# SOCDDR3Bank.net
KiCad netlist of a schematic drawn in Altium Designer
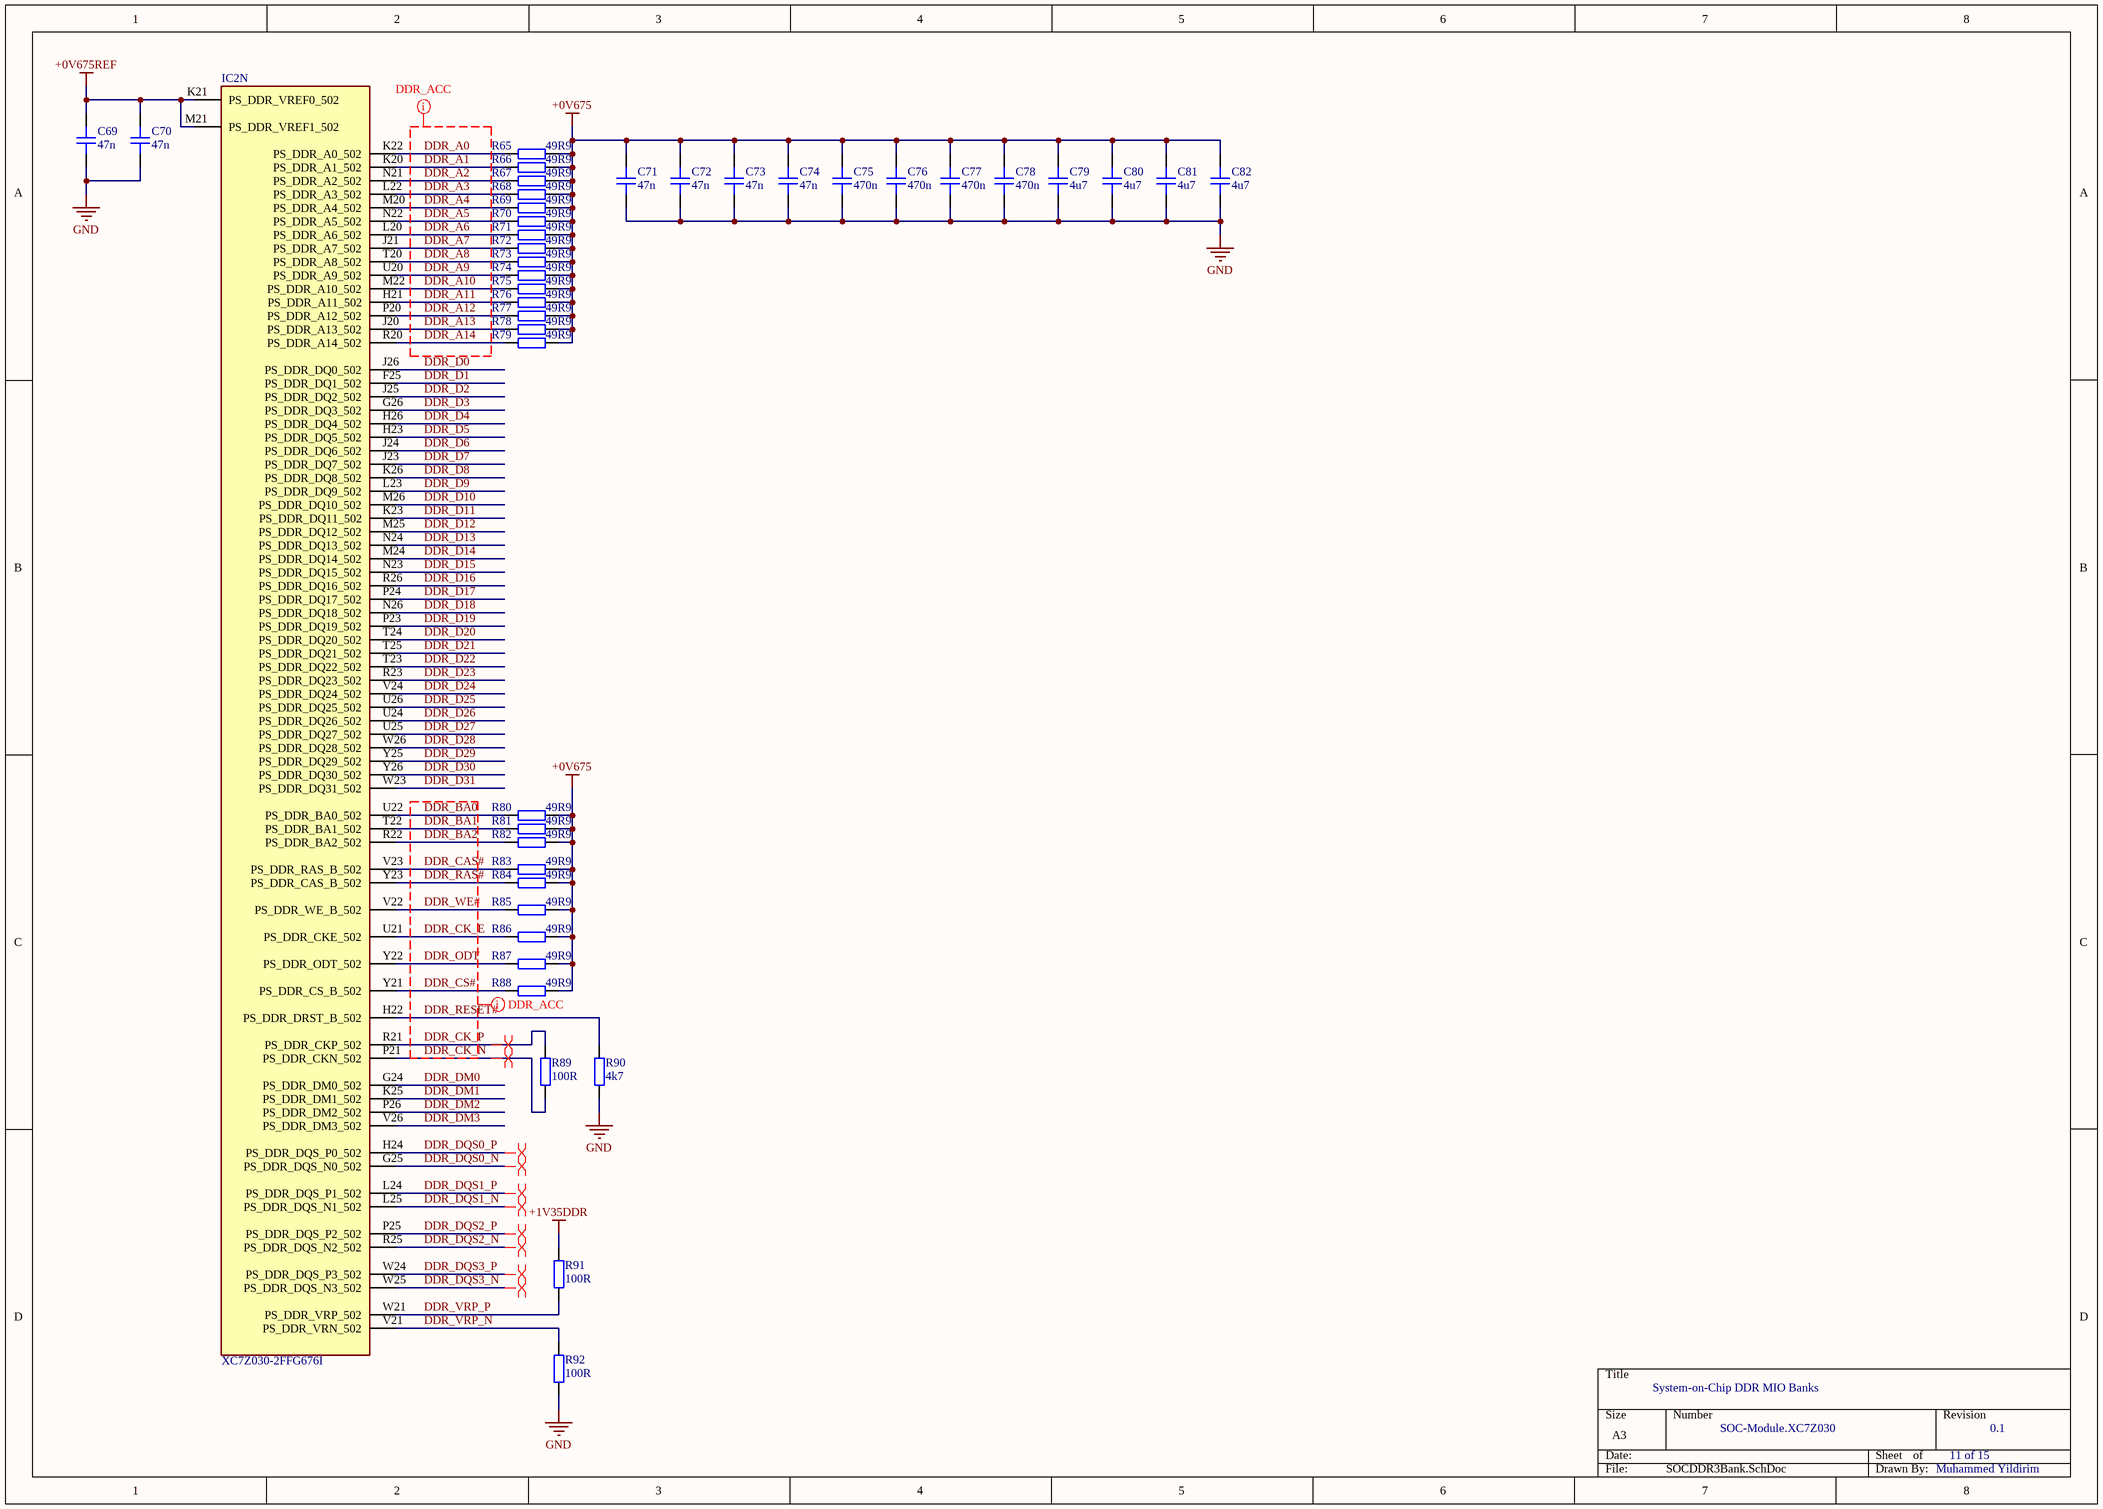
[diagram p0: SOCDDR3Bank.SchDoc]

(export (version "E")
  (design (tool "Eeschema 10.0.6"))
  (components
    (comp (ref "C69")
      (value "47n")
      (footprint "CAP_0201")
      (description "Capacitor SMD 0201")
      (libsource (lib "Schematic-Lib-PhilsLab") (part "CAP_0201"))
    )
    (comp (ref "C70")
      (value "47n")
      (footprint "CAP_0201")
      (description "Capacitor SMD 0201")
      (libsource (lib "Schematic-Lib-PhilsLab") (part "CAP_0201"))
    )
    (comp (ref "C71")
      (value "47n")
      (footprint "CAP_0201")
      (description "Capacitor SMD 0201")
      (libsource (lib "Schematic-Lib-PhilsLab") (part "CAP_0201"))
    )
    (comp (ref "C72")
      (value "47n")
      (footprint "CAP_0201")
      (description "Capacitor SMD 0201")
      (libsource (lib "Schematic-Lib-PhilsLab") (part "CAP_0201"))
    )
    (comp (ref "C73")
      (value "47n")
      (footprint "CAP_0201")
      (description "Capacitor SMD 0201")
      (libsource (lib "Schematic-Lib-PhilsLab") (part "CAP_0201"))
    )
    (comp (ref "C74")
      (value "47n")
      (footprint "CAP_0201")
      (description "Capacitor SMD 0201")
      (libsource (lib "Schematic-Lib-PhilsLab") (part "CAP_0201"))
    )
    (comp (ref "C75")
      (value "470n")
      (footprint "CAP_0201")
      (description "Capacitor SMD 0201")
      (libsource (lib "Schematic-Lib-PhilsLab") (part "CAP_0201"))
    )
    (comp (ref "C76")
      (value "470n")
      (footprint "CAP_0201")
      (description "Capacitor SMD 0201")
      (libsource (lib "Schematic-Lib-PhilsLab") (part "CAP_0201"))
    )
    (comp (ref "C77")
      (value "470n")
      (footprint "CAP_0201")
      (description "Capacitor SMD 0201")
      (libsource (lib "Schematic-Lib-PhilsLab") (part "CAP_0201"))
    )
    (comp (ref "C78")
      (value "470n")
      (footprint "CAP_0201")
      (description "Capacitor SMD 0201")
      (libsource (lib "Schematic-Lib-PhilsLab") (part "CAP_0201"))
    )
    (comp (ref "C79")
      (value "4u7")
      (footprint "CAP_0402")
      (description "Capacitor SMD 0402")
      (libsource (lib "Schematic-Lib-PhilsLab") (part "CAP_0402"))
    )
    (comp (ref "C80")
      (value "4u7")
      (footprint "CAP_0402")
      (description "Capacitor SMD 0402")
      (libsource (lib "Schematic-Lib-PhilsLab") (part "CAP_0402"))
    )
    (comp (ref "C81")
      (value "4u7")
      (footprint "CAP_0402")
      (description "Capacitor SMD 0402")
      (libsource (lib "Schematic-Lib-PhilsLab") (part "CAP_0402"))
    )
    (comp (ref "C82")
      (value "4u7")
      (footprint "CAP_0402")
      (description "Capacitor SMD 0402")
      (libsource (lib "Schematic-Lib-PhilsLab") (part "CAP_0402"))
    )
    (comp (ref "IC2")
      (value "XC7Z030-2FFG676I")
      (footprint "XC7Z030PCBLib:BGA676C100P26X26_2700X2700X324")
      (description "Integrated Circuit")
      (fields (field (name "MOUSER PART NUMBER") "217-XC7Z030-2FFG676I"))
      (libsource (lib "XC7Z030SCHLib") (part "XC7Z030-2FFG676I"))
    )
    (comp (ref "R65")
      (value "49R9")
      (footprint "RES_0201")
      (description "Resistor SMD 0201")
      (libsource (lib "Schematic-Lib-PhilsLab") (part "RES_0201"))
    )
    (comp (ref "R66")
      (value "49R9")
      (footprint "RES_0201")
      (description "Resistor SMD 0201")
      (libsource (lib "Schematic-Lib-PhilsLab") (part "RES_0201"))
    )
    (comp (ref "R67")
      (value "49R9")
      (footprint "RES_0201")
      (description "Resistor SMD 0201")
      (libsource (lib "Schematic-Lib-PhilsLab") (part "RES_0201"))
    )
    (comp (ref "R68")
      (value "49R9")
      (footprint "RES_0201")
      (description "Resistor SMD 0201")
      (libsource (lib "Schematic-Lib-PhilsLab") (part "RES_0201"))
    )
    (comp (ref "R69")
      (value "49R9")
      (footprint "RES_0201")
      (description "Resistor SMD 0201")
      (libsource (lib "Schematic-Lib-PhilsLab") (part "RES_0201"))
    )
    (comp (ref "R70")
      (value "49R9")
      (footprint "RES_0201")
      (description "Resistor SMD 0201")
      (libsource (lib "Schematic-Lib-PhilsLab") (part "RES_0201"))
    )
    (comp (ref "R71")
      (value "49R9")
      (footprint "RES_0201")
      (description "Resistor SMD 0201")
      (libsource (lib "Schematic-Lib-PhilsLab") (part "RES_0201"))
    )
    (comp (ref "R72")
      (value "49R9")
      (footprint "RES_0201")
      (description "Resistor SMD 0201")
      (libsource (lib "Schematic-Lib-PhilsLab") (part "RES_0201"))
    )
    (comp (ref "R73")
      (value "49R9")
      (footprint "RES_0201")
      (description "Resistor SMD 0201")
      (libsource (lib "Schematic-Lib-PhilsLab") (part "RES_0201"))
    )
    (comp (ref "R74")
      (value "49R9")
      (footprint "RES_0201")
      (description "Resistor SMD 0201")
      (libsource (lib "Schematic-Lib-PhilsLab") (part "RES_0201"))
    )
    (comp (ref "R75")
      (value "49R9")
      (footprint "RES_0201")
      (description "Resistor SMD 0201")
      (libsource (lib "Schematic-Lib-PhilsLab") (part "RES_0201"))
    )
    (comp (ref "R76")
      (value "49R9")
      (footprint "RES_0201")
      (description "Resistor SMD 0201")
      (libsource (lib "Schematic-Lib-PhilsLab") (part "RES_0201"))
    )
    (comp (ref "R77")
      (value "49R9")
      (footprint "RES_0201")
      (description "Resistor SMD 0201")
      (libsource (lib "Schematic-Lib-PhilsLab") (part "RES_0201"))
    )
    (comp (ref "R78")
      (value "49R9")
      (footprint "RES_0201")
      (description "Resistor SMD 0201")
      (libsource (lib "Schematic-Lib-PhilsLab") (part "RES_0201"))
    )
    (comp (ref "R79")
      (value "49R9")
      (footprint "RES_0201")
      (description "Resistor SMD 0201")
      (libsource (lib "Schematic-Lib-PhilsLab") (part "RES_0201"))
    )
    (comp (ref "R80")
      (value "49R9")
      (footprint "RES_0201")
      (description "Resistor SMD 0201")
      (libsource (lib "Schematic-Lib-PhilsLab") (part "RES_0201"))
    )
    (comp (ref "R81")
      (value "49R9")
      (footprint "RES_0201")
      (description "Resistor SMD 0201")
      (libsource (lib "Schematic-Lib-PhilsLab") (part "RES_0201"))
    )
    (comp (ref "R82")
      (value "49R9")
      (footprint "RES_0201")
      (description "Resistor SMD 0201")
      (libsource (lib "Schematic-Lib-PhilsLab") (part "RES_0201"))
    )
    (comp (ref "R83")
      (value "49R9")
      (footprint "RES_0201")
      (description "Resistor SMD 0201")
      (libsource (lib "Schematic-Lib-PhilsLab") (part "RES_0201"))
    )
    (comp (ref "R84")
      (value "49R9")
      (footprint "RES_0201")
      (description "Resistor SMD 0201")
      (libsource (lib "Schematic-Lib-PhilsLab") (part "RES_0201"))
    )
    (comp (ref "R85")
      (value "49R9")
      (footprint "RES_0201")
      (description "Resistor SMD 0201")
      (libsource (lib "Schematic-Lib-PhilsLab") (part "RES_0201"))
    )
    (comp (ref "R86")
      (value "49R9")
      (footprint "RES_0201")
      (description "Resistor SMD 0201")
      (libsource (lib "Schematic-Lib-PhilsLab") (part "RES_0201"))
    )
    (comp (ref "R87")
      (value "49R9")
      (footprint "RES_0201")
      (description "Resistor SMD 0201")
      (libsource (lib "Schematic-Lib-PhilsLab") (part "RES_0201"))
    )
    (comp (ref "R88")
      (value "49R9")
      (footprint "RES_0201")
      (description "Resistor SMD 0201")
      (libsource (lib "Schematic-Lib-PhilsLab") (part "RES_0201"))
    )
    (comp (ref "R89")
      (value "100R")
      (footprint "RES_0201")
      (description "Resistor SMD 0201")
      (libsource (lib "Schematic-Lib-PhilsLab") (part "RES_0201"))
    )
    (comp (ref "R90")
      (value "4k7")
      (footprint "RES_0201")
      (description "Resistor SMD 0201")
      (libsource (lib "Schematic-Lib-PhilsLab") (part "RES_0201"))
    )
    (comp (ref "R91")
      (value "100R")
      (footprint "RES_0201")
      (description "Resistor SMD 0201")
      (libsource (lib "Schematic-Lib-PhilsLab") (part "RES_0201"))
    )
    (comp (ref "R92")
      (value "100R")
      (footprint "RES_0201")
      (description "Resistor SMD 0201")
      (libsource (lib "Schematic-Lib-PhilsLab") (part "RES_0201"))
    )
  )
  (nets
    (net (code "1") (name "+0V675") (class "Default")
      (node (ref "C71") (pin "2") (pinfunction "2_2") (pintype "passive"))
      (node (ref "C72") (pin "2") (pinfunction "2_2") (pintype "passive"))
      (node (ref "C73") (pin "2") (pinfunction "2_2") (pintype "passive"))
      (node (ref "C74") (pin "2") (pinfunction "2_2") (pintype "passive"))
      (node (ref "C75") (pin "2") (pinfunction "2_2") (pintype "passive"))
      (node (ref "C76") (pin "2") (pinfunction "2_2") (pintype "passive"))
      (node (ref "C77") (pin "2") (pinfunction "2_2") (pintype "passive"))
      (node (ref "C78") (pin "2") (pinfunction "2_2") (pintype "passive"))
      (node (ref "C79") (pin "2") (pinfunction "2_2") (pintype "passive"))
      (node (ref "C80") (pin "2") (pinfunction "2_2") (pintype "passive"))
      (node (ref "C81") (pin "2") (pinfunction "2_2") (pintype "passive"))
      (node (ref "C82") (pin "2") (pinfunction "2_2") (pintype "passive"))
      (node (ref "R65") (pin "1") (pinfunction "1_1") (pintype "passive"))
      (node (ref "R66") (pin "1") (pinfunction "1_1") (pintype "passive"))
      (node (ref "R67") (pin "1") (pinfunction "1_1") (pintype "passive"))
      (node (ref "R68") (pin "1") (pinfunction "1_1") (pintype "passive"))
      (node (ref "R69") (pin "1") (pinfunction "1_1") (pintype "passive"))
      (node (ref "R70") (pin "1") (pinfunction "1_1") (pintype "passive"))
      (node (ref "R71") (pin "1") (pinfunction "1_1") (pintype "passive"))
      (node (ref "R72") (pin "1") (pinfunction "1_1") (pintype "passive"))
      (node (ref "R73") (pin "1") (pinfunction "1_1") (pintype "passive"))
      (node (ref "R74") (pin "1") (pinfunction "1_1") (pintype "passive"))
      (node (ref "R75") (pin "1") (pinfunction "1_1") (pintype "passive"))
      (node (ref "R76") (pin "1") (pinfunction "1_1") (pintype "passive"))
      (node (ref "R77") (pin "1") (pinfunction "1_1") (pintype "passive"))
      (node (ref "R78") (pin "1") (pinfunction "1_1") (pintype "passive"))
      (node (ref "R79") (pin "1") (pinfunction "1_1") (pintype "passive"))
      (node (ref "R80") (pin "1") (pinfunction "1_1") (pintype "passive"))
      (node (ref "R81") (pin "1") (pinfunction "1_1") (pintype "passive"))
      (node (ref "R82") (pin "1") (pinfunction "1_1") (pintype "passive"))
      (node (ref "R83") (pin "1") (pinfunction "1_1") (pintype "passive"))
      (node (ref "R84") (pin "1") (pinfunction "1_1") (pintype "passive"))
      (node (ref "R85") (pin "1") (pinfunction "1_1") (pintype "passive"))
      (node (ref "R86") (pin "1") (pinfunction "1_1") (pintype "passive"))
      (node (ref "R87") (pin "1") (pinfunction "1_1") (pintype "passive"))
      (node (ref "R88") (pin "1") (pinfunction "1_1") (pintype "passive"))
    )
    (net (code "2") (name "+0V675REF") (class "Default")
      (node (ref "C69") (pin "2") (pinfunction "2_2") (pintype "passive"))
      (node (ref "C70") (pin "2") (pinfunction "2_2") (pintype "passive"))
      (node (ref "IC2") (pin "K21") (pinfunction "PS_DDR_VREF0_502_K21") (pintype "passive"))
      (node (ref "IC2") (pin "M21") (pinfunction "PS_DDR_VREF1_502_M21") (pintype "passive"))
    )
    (net (code "3") (name "+1V35DDR") (class "Default")
      (node (ref "R91") (pin "2") (pinfunction "2_2") (pintype "passive"))
    )
    (net (code "4") (name "/DDR_A0") (class "Default")
      (node (ref "IC2") (pin "K22") (pinfunction "PS_DDR_A0_502_K22") (pintype "passive"))
      (node (ref "R65") (pin "2") (pinfunction "2_2") (pintype "passive"))
    )
    (net (code "5") (name "/DDR_A1") (class "Default")
      (node (ref "IC2") (pin "K20") (pinfunction "PS_DDR_A1_502_K20") (pintype "passive"))
      (node (ref "R66") (pin "2") (pinfunction "2_2") (pintype "passive"))
    )
    (net (code "6") (name "/DDR_A2") (class "Default")
      (node (ref "IC2") (pin "N21") (pinfunction "PS_DDR_A2_502_N21") (pintype "passive"))
      (node (ref "R67") (pin "2") (pinfunction "2_2") (pintype "passive"))
    )
    (net (code "7") (name "/DDR_A3") (class "Default")
      (node (ref "IC2") (pin "L22") (pinfunction "PS_DDR_A3_502_L22") (pintype "passive"))
      (node (ref "R68") (pin "2") (pinfunction "2_2") (pintype "passive"))
    )
    (net (code "8") (name "/DDR_A4") (class "Default")
      (node (ref "IC2") (pin "M20") (pinfunction "PS_DDR_A4_502_M20") (pintype "passive"))
      (node (ref "R69") (pin "2") (pinfunction "2_2") (pintype "passive"))
    )
    (net (code "9") (name "/DDR_A5") (class "Default")
      (node (ref "IC2") (pin "N22") (pinfunction "PS_DDR_A5_502_N22") (pintype "passive"))
      (node (ref "R70") (pin "2") (pinfunction "2_2") (pintype "passive"))
    )
    (net (code "10") (name "/DDR_A6") (class "Default")
      (node (ref "IC2") (pin "L20") (pinfunction "PS_DDR_A6_502_L20") (pintype "passive"))
      (node (ref "R71") (pin "2") (pinfunction "2_2") (pintype "passive"))
    )
    (net (code "11") (name "/DDR_A7") (class "Default")
      (node (ref "IC2") (pin "J21") (pinfunction "PS_DDR_A7_502_J21") (pintype "passive"))
      (node (ref "R72") (pin "2") (pinfunction "2_2") (pintype "passive"))
    )
    (net (code "12") (name "/DDR_A8") (class "Default")
      (node (ref "IC2") (pin "T20") (pinfunction "PS_DDR_A8_502_T20") (pintype "passive"))
      (node (ref "R73") (pin "2") (pinfunction "2_2") (pintype "passive"))
    )
    (net (code "13") (name "/DDR_A9") (class "Default")
      (node (ref "IC2") (pin "U20") (pinfunction "PS_DDR_A9_502_U20") (pintype "passive"))
      (node (ref "R74") (pin "2") (pinfunction "2_2") (pintype "passive"))
    )
    (net (code "14") (name "/DDR_A10") (class "Default")
      (node (ref "IC2") (pin "M22") (pinfunction "PS_DDR_A10_502_M22") (pintype "passive"))
      (node (ref "R75") (pin "2") (pinfunction "2_2") (pintype "passive"))
    )
    (net (code "15") (name "/DDR_A11") (class "Default")
      (node (ref "IC2") (pin "H21") (pinfunction "PS_DDR_A11_502_H21") (pintype "passive"))
      (node (ref "R76") (pin "2") (pinfunction "2_2") (pintype "passive"))
    )
    (net (code "16") (name "/DDR_A12") (class "Default")
      (node (ref "IC2") (pin "P20") (pinfunction "PS_DDR_A12_502_P20") (pintype "passive"))
      (node (ref "R77") (pin "2") (pinfunction "2_2") (pintype "passive"))
    )
    (net (code "17") (name "/DDR_A13") (class "Default")
      (node (ref "IC2") (pin "J20") (pinfunction "PS_DDR_A13_502_J20") (pintype "passive"))
      (node (ref "R78") (pin "2") (pinfunction "2_2") (pintype "passive"))
    )
    (net (code "18") (name "/DDR_A14") (class "Default")
      (node (ref "IC2") (pin "R20") (pinfunction "PS_DDR_A14_502_R20") (pintype "passive"))
      (node (ref "R79") (pin "2") (pinfunction "2_2") (pintype "passive"))
    )
    (net (code "19") (name "/DDR_BA0") (class "Default")
      (node (ref "IC2") (pin "U22") (pinfunction "PS_DDR_BA0_502_U22") (pintype "passive"))
      (node (ref "R80") (pin "2") (pinfunction "2_2") (pintype "passive"))
    )
    (net (code "20") (name "/DDR_BA1") (class "Default")
      (node (ref "IC2") (pin "T22") (pinfunction "PS_DDR_BA1_502_T22") (pintype "passive"))
      (node (ref "R81") (pin "2") (pinfunction "2_2") (pintype "passive"))
    )
    (net (code "21") (name "/DDR_BA2") (class "Default")
      (node (ref "IC2") (pin "R22") (pinfunction "PS_DDR_BA2_502_R22") (pintype "passive"))
      (node (ref "R82") (pin "2") (pinfunction "2_2") (pintype "passive"))
    )
    (net (code "22") (name "/DDR_CAS#") (class "Default")
      (node (ref "IC2") (pin "V23") (pinfunction "PS_DDR_RAS_B_502_V23") (pintype "passive"))
      (node (ref "R83") (pin "2") (pinfunction "2_2") (pintype "passive"))
    )
    (net (code "23") (name "/DDR_CK_E") (class "Default")
      (node (ref "IC2") (pin "U21") (pinfunction "PS_DDR_CKE_502_U21") (pintype "passive"))
      (node (ref "R86") (pin "2") (pinfunction "2_2") (pintype "passive"))
    )
    (net (code "24") (name "/DDR_CK_N") (class "Default")
      (node (ref "IC2") (pin "P21") (pinfunction "PS_DDR_CKN_502_P21") (pintype "passive"))
      (node (ref "R89") (pin "1") (pinfunction "1_1") (pintype "passive"))
    )
    (net (code "25") (name "/DDR_CK_P") (class "Default")
      (node (ref "IC2") (pin "R21") (pinfunction "PS_DDR_CKP_502_R21") (pintype "passive"))
      (node (ref "R89") (pin "2") (pinfunction "2_2") (pintype "passive"))
    )
    (net (code "26") (name "/DDR_CS#") (class "Default")
      (node (ref "IC2") (pin "Y21") (pinfunction "PS_DDR_CS_B_502_Y21") (pintype "passive"))
      (node (ref "R88") (pin "2") (pinfunction "2_2") (pintype "passive"))
    )
    (net (code "27") (name "/DDR_D0") (class "Default")
      (node (ref "IC2") (pin "J26") (pinfunction "PS_DDR_DQ0_502_J26") (pintype "passive"))
    )
    (net (code "28") (name "/DDR_D1") (class "Default")
      (node (ref "IC2") (pin "F25") (pinfunction "PS_DDR_DQ1_502_F25") (pintype "passive"))
    )
    (net (code "29") (name "/DDR_D2") (class "Default")
      (node (ref "IC2") (pin "J25") (pinfunction "PS_DDR_DQ2_502_J25") (pintype "passive"))
    )
    (net (code "30") (name "/DDR_D3") (class "Default")
      (node (ref "IC2") (pin "G26") (pinfunction "PS_DDR_DQ3_502_G26") (pintype "passive"))
    )
    (net (code "31") (name "/DDR_D4") (class "Default")
      (node (ref "IC2") (pin "H26") (pinfunction "PS_DDR_DQ4_502_H26") (pintype "passive"))
    )
    (net (code "32") (name "/DDR_D5") (class "Default")
      (node (ref "IC2") (pin "H23") (pinfunction "PS_DDR_DQ5_502_H23") (pintype "passive"))
    )
    (net (code "33") (name "/DDR_D6") (class "Default")
      (node (ref "IC2") (pin "J24") (pinfunction "PS_DDR_DQ6_502_J24") (pintype "passive"))
    )
    (net (code "34") (name "/DDR_D7") (class "Default")
      (node (ref "IC2") (pin "J23") (pinfunction "PS_DDR_DQ7_502_J23") (pintype "passive"))
    )
    (net (code "35") (name "/DDR_D8") (class "Default")
      (node (ref "IC2") (pin "K26") (pinfunction "PS_DDR_DQ8_502_K26") (pintype "passive"))
    )
    (net (code "36") (name "/DDR_D9") (class "Default")
      (node (ref "IC2") (pin "L23") (pinfunction "PS_DDR_DQ9_502_L23") (pintype "passive"))
    )
    (net (code "37") (name "/DDR_D10") (class "Default")
      (node (ref "IC2") (pin "M26") (pinfunction "PS_DDR_DQ10_502_M26") (pintype "passive"))
    )
    (net (code "38") (name "/DDR_D11") (class "Default")
      (node (ref "IC2") (pin "K23") (pinfunction "PS_DDR_DQ11_502_K23") (pintype "passive"))
    )
    (net (code "39") (name "/DDR_D12") (class "Default")
      (node (ref "IC2") (pin "M25") (pinfunction "PS_DDR_DQ12_502_M25") (pintype "passive"))
    )
    (net (code "40") (name "/DDR_D13") (class "Default")
      (node (ref "IC2") (pin "N24") (pinfunction "PS_DDR_DQ13_502_N24") (pintype "passive"))
    )
    (net (code "41") (name "/DDR_D14") (class "Default")
      (node (ref "IC2") (pin "M24") (pinfunction "PS_DDR_DQ14_502_M24") (pintype "passive"))
    )
    (net (code "42") (name "/DDR_D15") (class "Default")
      (node (ref "IC2") (pin "N23") (pinfunction "PS_DDR_DQ15_502_N23") (pintype "passive"))
    )
    (net (code "43") (name "/DDR_D16") (class "Default")
      (node (ref "IC2") (pin "R26") (pinfunction "PS_DDR_DQ16_502_R26") (pintype "passive"))
    )
    (net (code "44") (name "/DDR_D17") (class "Default")
      (node (ref "IC2") (pin "P24") (pinfunction "PS_DDR_DQ17_502_P24") (pintype "passive"))
    )
    (net (code "45") (name "/DDR_D18") (class "Default")
      (node (ref "IC2") (pin "N26") (pinfunction "PS_DDR_DQ18_502_N26") (pintype "passive"))
    )
    (net (code "46") (name "/DDR_D19") (class "Default")
      (node (ref "IC2") (pin "P23") (pinfunction "PS_DDR_DQ19_502_P23") (pintype "passive"))
    )
    (net (code "47") (name "/DDR_D20") (class "Default")
      (node (ref "IC2") (pin "T24") (pinfunction "PS_DDR_DQ20_502_T24") (pintype "passive"))
    )
    (net (code "48") (name "/DDR_D21") (class "Default")
      (node (ref "IC2") (pin "T25") (pinfunction "PS_DDR_DQ21_502_T25") (pintype "passive"))
    )
    (net (code "49") (name "/DDR_D22") (class "Default")
      (node (ref "IC2") (pin "T23") (pinfunction "PS_DDR_DQ22_502_T23") (pintype "passive"))
    )
    (net (code "50") (name "/DDR_D23") (class "Default")
      (node (ref "IC2") (pin "R23") (pinfunction "PS_DDR_DQ23_502_R23") (pintype "passive"))
    )
    (net (code "51") (name "/DDR_D24") (class "Default")
      (node (ref "IC2") (pin "V24") (pinfunction "PS_DDR_DQ24_502_V24") (pintype "passive"))
    )
    (net (code "52") (name "/DDR_D25") (class "Default")
      (node (ref "IC2") (pin "U26") (pinfunction "PS_DDR_DQ25_502_U26") (pintype "passive"))
    )
    (net (code "53") (name "/DDR_D26") (class "Default")
      (node (ref "IC2") (pin "U24") (pinfunction "PS_DDR_DQ26_502_U24") (pintype "passive"))
    )
    (net (code "54") (name "/DDR_D27") (class "Default")
      (node (ref "IC2") (pin "U25") (pinfunction "PS_DDR_DQ27_502_U25") (pintype "passive"))
    )
    (net (code "55") (name "/DDR_D28") (class "Default")
      (node (ref "IC2") (pin "W26") (pinfunction "PS_DDR_DQ28_502_W26") (pintype "passive"))
    )
    (net (code "56") (name "/DDR_D29") (class "Default")
      (node (ref "IC2") (pin "Y25") (pinfunction "PS_DDR_DQ29_502_Y25") (pintype "passive"))
    )
    (net (code "57") (name "/DDR_D30") (class "Default")
      (node (ref "IC2") (pin "Y26") (pinfunction "PS_DDR_DQ30_502_Y26") (pintype "passive"))
    )
    (net (code "58") (name "/DDR_D31") (class "Default")
      (node (ref "IC2") (pin "W23") (pinfunction "PS_DDR_DQ31_502_W23") (pintype "passive"))
    )
    (net (code "59") (name "/DDR_DM0") (class "Default")
      (node (ref "IC2") (pin "G24") (pinfunction "PS_DDR_DM0_502_G24") (pintype "passive"))
    )
    (net (code "60") (name "/DDR_DM1") (class "Default")
      (node (ref "IC2") (pin "K25") (pinfunction "PS_DDR_DM1_502_K25") (pintype "passive"))
    )
    (net (code "61") (name "/DDR_DM2") (class "Default")
      (node (ref "IC2") (pin "P26") (pinfunction "PS_DDR_DM2_502_P26") (pintype "passive"))
    )
    (net (code "62") (name "/DDR_DM3") (class "Default")
      (node (ref "IC2") (pin "V26") (pinfunction "PS_DDR_DM3_502_V26") (pintype "passive"))
    )
    (net (code "63") (name "/DDR_DQS0_N") (class "Default")
      (node (ref "IC2") (pin "G25") (pinfunction "PS_DDR_DQS_N0_502_G25") (pintype "passive"))
    )
    (net (code "64") (name "/DDR_DQS0_P") (class "Default")
      (node (ref "IC2") (pin "H24") (pinfunction "PS_DDR_DQS_P0_502_H24") (pintype "passive"))
    )
    (net (code "65") (name "/DDR_DQS1_N") (class "Default")
      (node (ref "IC2") (pin "L25") (pinfunction "PS_DDR_DQS_N1_502_L25") (pintype "passive"))
    )
    (net (code "66") (name "/DDR_DQS1_P") (class "Default")
      (node (ref "IC2") (pin "L24") (pinfunction "PS_DDR_DQS_P1_502_L24") (pintype "passive"))
    )
    (net (code "67") (name "/DDR_DQS2_N") (class "Default")
      (node (ref "IC2") (pin "R25") (pinfunction "PS_DDR_DQS_N2_502_R25") (pintype "passive"))
    )
    (net (code "68") (name "/DDR_DQS2_P") (class "Default")
      (node (ref "IC2") (pin "P25") (pinfunction "PS_DDR_DQS_P2_502_P25") (pintype "passive"))
    )
    (net (code "69") (name "/DDR_DQS3_N") (class "Default")
      (node (ref "IC2") (pin "W25") (pinfunction "PS_DDR_DQS_N3_502_W25") (pintype "passive"))
    )
    (net (code "70") (name "/DDR_DQS3_P") (class "Default")
      (node (ref "IC2") (pin "W24") (pinfunction "PS_DDR_DQS_P3_502_W24") (pintype "passive"))
    )
    (net (code "71") (name "/DDR_ODT") (class "Default")
      (node (ref "IC2") (pin "Y22") (pinfunction "PS_DDR_ODT_502_Y22") (pintype "passive"))
      (node (ref "R87") (pin "2") (pinfunction "2_2") (pintype "passive"))
    )
    (net (code "72") (name "/DDR_RAS#") (class "Default")
      (node (ref "IC2") (pin "Y23") (pinfunction "PS_DDR_CAS_B_502_Y23") (pintype "passive"))
      (node (ref "R84") (pin "2") (pinfunction "2_2") (pintype "passive"))
    )
    (net (code "73") (name "/DDR_RESET#") (class "Default")
      (node (ref "IC2") (pin "H22") (pinfunction "PS_DDR_DRST_B_502_H22") (pintype "passive"))
      (node (ref "R90") (pin "2") (pinfunction "2_2") (pintype "passive"))
    )
    (net (code "74") (name "/DDR_VRP_N") (class "Default")
      (node (ref "IC2") (pin "V21") (pinfunction "PS_DDR_VRN_502_V21") (pintype "passive"))
      (node (ref "R92") (pin "2") (pinfunction "2_2") (pintype "passive"))
    )
    (net (code "75") (name "/DDR_VRP_P") (class "Default")
      (node (ref "IC2") (pin "W21") (pinfunction "PS_DDR_VRP_502_W21") (pintype "passive"))
      (node (ref "R91") (pin "1") (pinfunction "1_1") (pintype "passive"))
    )
    (net (code "76") (name "/DDR_WE#") (class "Default")
      (node (ref "IC2") (pin "V22") (pinfunction "PS_DDR_WE_B_502_V22") (pintype "passive"))
      (node (ref "R85") (pin "2") (pinfunction "2_2") (pintype "passive"))
    )
    (net (code "77") (name "GND") (class "Default")
      (node (ref "C69") (pin "1") (pinfunction "1_1") (pintype "passive"))
      (node (ref "C70") (pin "1") (pinfunction "1_1") (pintype "passive"))
      (node (ref "C71") (pin "1") (pinfunction "1_1") (pintype "passive"))
      (node (ref "C72") (pin "1") (pinfunction "1_1") (pintype "passive"))
      (node (ref "C73") (pin "1") (pinfunction "1_1") (pintype "passive"))
      (node (ref "C74") (pin "1") (pinfunction "1_1") (pintype "passive"))
      (node (ref "C75") (pin "1") (pinfunction "1_1") (pintype "passive"))
      (node (ref "C76") (pin "1") (pinfunction "1_1") (pintype "passive"))
      (node (ref "C77") (pin "1") (pinfunction "1_1") (pintype "passive"))
      (node (ref "C78") (pin "1") (pinfunction "1_1") (pintype "passive"))
      (node (ref "C79") (pin "1") (pinfunction "1_1") (pintype "passive"))
      (node (ref "C80") (pin "1") (pinfunction "1_1") (pintype "passive"))
      (node (ref "C81") (pin "1") (pinfunction "1_1") (pintype "passive"))
      (node (ref "C82") (pin "1") (pinfunction "1_1") (pintype "passive"))
      (node (ref "R90") (pin "1") (pinfunction "1_1") (pintype "passive"))
      (node (ref "R92") (pin "1") (pinfunction "1_1") (pintype "passive"))
    )
  )
)
